# 15-MT7688AN_Ethernet-E.net
KiCad netlist of a schematic drawn in Altium Designer
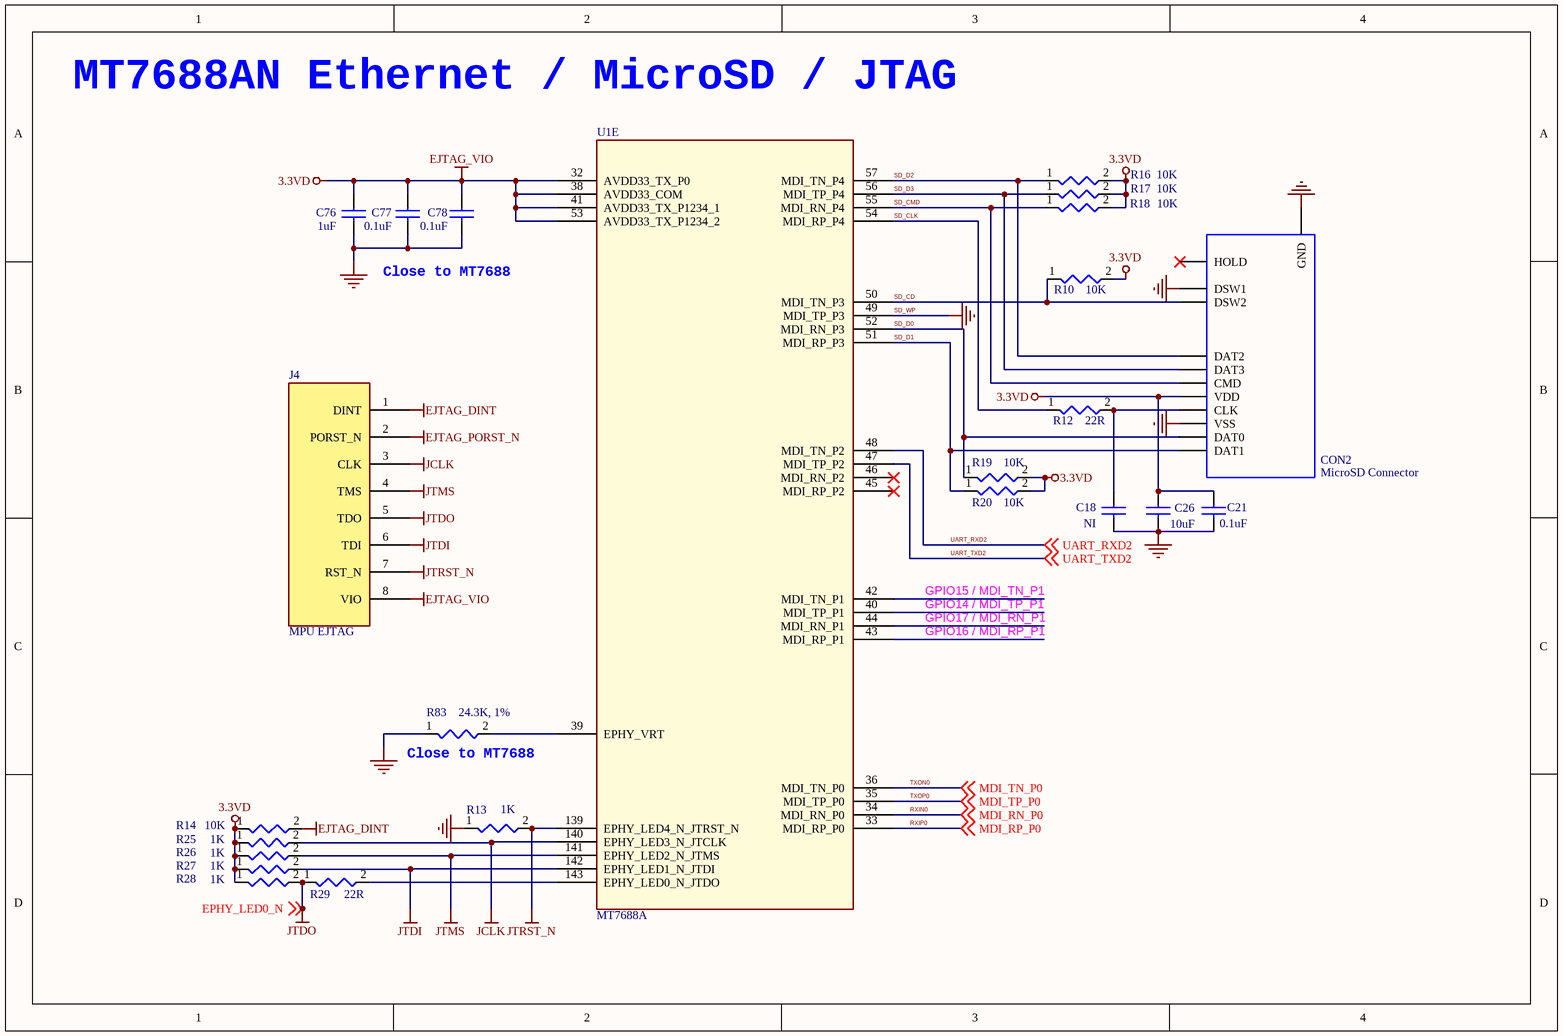
[diagram p0: 15-MT7688AN Ethernet-E.SchDoc]

(export (version "E")
  (design (tool "Eeschema 10.0.6"))
  (components
    (comp (ref "C18")
      (value "NI")
      (footprint "RLC 0201 M35")
      (libsource (lib "LinkIt Air+ (EK-7688AM+)") (part "CAP NP"))
    )
    (comp (ref "C21")
      (value "0.1uF")
      (footprint "RLC 0201 M35")
      (libsource (lib "LinkIt Air+ (EK-7688AM+)") (part "CAP NP"))
    )
    (comp (ref "C26")
      (value "10uF")
      (footprint "RLC 0402 M35")
      (libsource (lib "LinkIt Air+ (EK-7688AM+)") (part "CAP NP"))
    )
    (comp (ref "C76")
      (value "1uF")
      (footprint "RLC 0201 M35")
      (libsource (lib "LinkIt Air+ (EK-7688AM+)") (part "CAP NP"))
    )
    (comp (ref "C77")
      (value "0.1uF")
      (footprint "RLC 0201 M35")
      (libsource (lib "LinkIt Air+ (EK-7688AM+)") (part "CAP NP"))
    )
    (comp (ref "C78")
      (value "0.1uF")
      (footprint "RLC 0201 M35")
      (libsource (lib "LinkIt Air+ (EK-7688AM+)") (part "CAP NP"))
    )
    (comp (ref "CON2")
      (value "MicroSD Connector")
      (footprint "MICROSD-ST11S008V4H")
      (description "Micro SD Card H=1.25 (ST11S008V4H)")
      (libsource (lib "LinkIt Air+ (EK-7688AM+)") (part "MicroSD-ST11S008V4H"))
    )
    (comp (ref "J4")
      (value "MPU EJTAG")
      (footprint "MPU EJTAG")
      (libsource (lib "LinkIt Air+ (EK-7688AM+)") (part "MPU EJTAG"))
    )
    (comp (ref "R10")
      (value "10K")
      (footprint "RLC 0201 M35")
      (libsource (lib "LinkIt Air+ (EK-7688AM+)") (part "RES/0402_3"))
    )
    (comp (ref "R12")
      (value "22R")
      (footprint "RLC 0201 M35")
      (libsource (lib "LinkIt Air+ (EK-7688AM+)") (part "RES/0402_3"))
    )
    (comp (ref "R13")
      (value "1K")
      (footprint "RLC 0201 M35")
      (libsource (lib "LinkIt Air+ (EK-7688AM+)") (part "RES/0402_3"))
    )
    (comp (ref "R14")
      (value "10K")
      (footprint "RLC 0201 M35")
      (libsource (lib "LinkIt Air+ (EK-7688AM+)") (part "RES/0402_3"))
    )
    (comp (ref "R16")
      (value "10K")
      (footprint "RLC 0201 M35")
      (libsource (lib "LinkIt Air+ (EK-7688AM+)") (part "RES/0402_3"))
    )
    (comp (ref "R17")
      (value "10K")
      (footprint "RLC 0201 M35")
      (libsource (lib "LinkIt Air+ (EK-7688AM+)") (part "RES/0402_3"))
    )
    (comp (ref "R18")
      (value "10K")
      (footprint "RLC 0201 M35")
      (libsource (lib "LinkIt Air+ (EK-7688AM+)") (part "RES/0402_3"))
    )
    (comp (ref "R19")
      (value "10K")
      (footprint "RLC 0201 M35")
      (libsource (lib "LinkIt Air+ (EK-7688AM+)") (part "RES/0402_3"))
    )
    (comp (ref "R20")
      (value "10K")
      (footprint "RLC 0201 M35")
      (libsource (lib "LinkIt Air+ (EK-7688AM+)") (part "RES/0402_3"))
    )
    (comp (ref "R25")
      (value "1K")
      (footprint "RLC 0201 M35")
      (libsource (lib "LinkIt Air+ (EK-7688AM+)") (part "RES/0402_3"))
    )
    (comp (ref "R26")
      (value "1K")
      (footprint "RLC 0201 M35")
      (libsource (lib "LinkIt Air+ (EK-7688AM+)") (part "RES/0402_3"))
    )
    (comp (ref "R27")
      (value "1K")
      (footprint "RLC 0201 M35")
      (libsource (lib "LinkIt Air+ (EK-7688AM+)") (part "RES/0402_3"))
    )
    (comp (ref "R28")
      (value "1K")
      (footprint "RLC 0201 M35")
      (libsource (lib "LinkIt Air+ (EK-7688AM+)") (part "RES/0402_3"))
    )
    (comp (ref "R29")
      (value "22R")
      (footprint "RLC 0201 M35")
      (libsource (lib "LinkIt Air+ (EK-7688AM+)") (part "RES/0402_3"))
    )
    (comp (ref "R83")
      (value "24.3K, 1%")
      (footprint "RLC 0201 M35")
      (libsource (lib "LinkIt Air+ (EK-7688AM+)") (part "RES/0402_3"))
    )
    (comp (ref "U1")
      (value "MT7688A")
      (footprint "MT7628AN$2F$DRQFN156$2F$SMD$2F$P0.5$2F$12X12")
      (libsource (lib "LinkIt Air+ (EK-7688AM+)") (part "MT7620N-n_26"))
    )
  )
  (nets
    (net (code "1") (name "/GPIO14 {slash} MDI_TP_P1") (class "Default")
      (node (ref "U1") (pin "40") (pinfunction "MDI_TP_P1_40") (pintype "passive"))
    )
    (net (code "2") (name "/GPIO15 {slash} MDI_TN_P1") (class "Default")
      (node (ref "U1") (pin "42") (pinfunction "MDI_TN_P1_42") (pintype "passive"))
    )
    (net (code "3") (name "/GPIO16 {slash} MDI_RP_P1") (class "Default")
      (node (ref "U1") (pin "43") (pinfunction "MDI_RP_P1_43") (pintype "passive"))
    )
    (net (code "4") (name "/GPIO17 {slash} MDI_RN_P1") (class "Default")
      (node (ref "U1") (pin "44") (pinfunction "MDI_RN_P1_44") (pintype "passive"))
    )
    (net (code "5") (name "/SD_CD") (class "Default")
      (node (ref "CON2") (pin "10") (pinfunction "DSW2_10") (pintype "passive"))
      (node (ref "R10") (pin "1") (pinfunction "1_1") (pintype "passive"))
      (node (ref "U1") (pin "50") (pinfunction "MDI_TN_P3_50") (pintype "passive"))
    )
    (net (code "6") (name "/SD_CLK") (class "Default")
      (node (ref "R12") (pin "1") (pinfunction "1_1") (pintype "passive"))
      (node (ref "U1") (pin "54") (pinfunction "MDI_RP_P4_54") (pintype "passive"))
    )
    (net (code "7") (name "/SD_CMD") (class "Default")
      (node (ref "CON2") (pin "3") (pinfunction "CMD_3") (pintype "passive"))
      (node (ref "R18") (pin "1") (pinfunction "1_1") (pintype "passive"))
      (node (ref "U1") (pin "55") (pinfunction "MDI_RN_P4_55") (pintype "passive"))
    )
    (net (code "8") (name "/SD_D0") (class "Default")
      (node (ref "CON2") (pin "7") (pinfunction "DAT0_7") (pintype "passive"))
      (node (ref "R19") (pin "1") (pinfunction "1_1") (pintype "passive"))
      (node (ref "U1") (pin "52") (pinfunction "MDI_RN_P3_52") (pintype "passive"))
    )
    (net (code "9") (name "/SD_D1") (class "Default")
      (node (ref "CON2") (pin "8") (pinfunction "DAT1_8") (pintype "passive"))
      (node (ref "R20") (pin "1") (pinfunction "1_1") (pintype "passive"))
      (node (ref "U1") (pin "51") (pinfunction "MDI_RP_P3_51") (pintype "passive"))
    )
    (net (code "10") (name "/SD_D2") (class "Default")
      (node (ref "CON2") (pin "1") (pinfunction "DAT2_1") (pintype "passive"))
      (node (ref "R16") (pin "1") (pinfunction "1_1") (pintype "passive"))
      (node (ref "U1") (pin "57") (pinfunction "MDI_TN_P4_57") (pintype "passive"))
    )
    (net (code "11") (name "/SD_D3") (class "Default")
      (node (ref "CON2") (pin "2") (pinfunction "DAT3_2") (pintype "passive"))
      (node (ref "R17") (pin "1") (pinfunction "1_1") (pintype "passive"))
      (node (ref "U1") (pin "56") (pinfunction "MDI_TP_P4_56") (pintype "passive"))
    )
    (net (code "12") (name "3.3VD") (class "Default")
      (node (ref "C21") (pin "1") (pinfunction "1_1") (pintype "passive"))
      (node (ref "C26") (pin "1") (pinfunction "1_1") (pintype "passive"))
      (node (ref "C76") (pin "1") (pinfunction "1_1") (pintype "passive"))
      (node (ref "C77") (pin "1") (pinfunction "1_1") (pintype "passive"))
      (node (ref "C78") (pin "1") (pinfunction "1_1") (pintype "passive"))
      (node (ref "CON2") (pin "4") (pinfunction "VDD_4") (pintype "passive"))
      (node (ref "J4") (pin "8") (pinfunction "VIO_8") (pintype "passive"))
      (node (ref "R10") (pin "2") (pinfunction "2_2") (pintype "passive"))
      (node (ref "R14") (pin "1") (pinfunction "1_1") (pintype "passive"))
      (node (ref "R16") (pin "2") (pinfunction "2_2") (pintype "passive"))
      (node (ref "R17") (pin "2") (pinfunction "2_2") (pintype "passive"))
      (node (ref "R18") (pin "2") (pinfunction "2_2") (pintype "passive"))
      (node (ref "R19") (pin "2") (pinfunction "2_2") (pintype "passive"))
      (node (ref "R20") (pin "2") (pinfunction "2_2") (pintype "passive"))
      (node (ref "R25") (pin "1") (pinfunction "1_1") (pintype "passive"))
      (node (ref "R26") (pin "1") (pinfunction "1_1") (pintype "passive"))
      (node (ref "R27") (pin "1") (pinfunction "1_1") (pintype "passive"))
      (node (ref "R28") (pin "1") (pinfunction "1_1") (pintype "passive"))
      (node (ref "U1") (pin "32") (pinfunction "AVDD33_TX_P0_32") (pintype "power_in"))
      (node (ref "U1") (pin "38") (pinfunction "AVDD33_COM_38") (pintype "power_in"))
      (node (ref "U1") (pin "41") (pinfunction "AVDD33_TX_P1234_1_41") (pintype "power_in"))
      (node (ref "U1") (pin "53") (pinfunction "AVDD33_TX_P1234_2_53") (pintype "power_in"))
    )
    (net (code "13") (name "EJTAG_DINT") (class "Default")
      (node (ref "J4") (pin "1") (pinfunction "DINT_1") (pintype "passive"))
      (node (ref "R14") (pin "2") (pinfunction "2_2") (pintype "passive"))
    )
    (net (code "14") (name "EJTAG_PORST_N") (class "Default")
      (node (ref "J4") (pin "2") (pinfunction "PORST_N_2") (pintype "passive"))
    )
    (net (code "15") (name "EPHY_LED0_N") (class "Default")
      (node (ref "J4") (pin "5") (pinfunction "TDO_5") (pintype "passive"))
      (node (ref "R28") (pin "2") (pinfunction "2_2") (pintype "passive"))
      (node (ref "R29") (pin "1") (pinfunction "1_1") (pintype "passive"))
    )
    (net (code "16") (name "GND") (class "Default")
      (node (ref "C18") (pin "2") (pinfunction "2_2") (pintype "passive"))
      (node (ref "C21") (pin "2") (pinfunction "2_2") (pintype "passive"))
      (node (ref "C26") (pin "2") (pinfunction "2_2") (pintype "passive"))
      (node (ref "C76") (pin "2") (pinfunction "2_2") (pintype "passive"))
      (node (ref "C77") (pin "2") (pinfunction "2_2") (pintype "passive"))
      (node (ref "C78") (pin "2") (pinfunction "2_2") (pintype "passive"))
      (node (ref "CON2") (pin "11") (pinfunction "DSW1_11") (pintype "passive"))
      (node (ref "CON2") (pin "14") (pinfunction "GND_14") (pintype "passive"))
      (node (ref "CON2") (pin "6") (pinfunction "VSS_6") (pintype "passive"))
      (node (ref "R13") (pin "1") (pinfunction "1_1") (pintype "passive"))
      (node (ref "R83") (pin "1") (pinfunction "1_1") (pintype "passive"))
      (node (ref "U1") (pin "49") (pinfunction "MDI_TP_P3_49") (pintype "passive"))
    )
    (net (code "17") (name "JCLK") (class "Default")
      (node (ref "J4") (pin "3") (pinfunction "CLK_3") (pintype "passive"))
      (node (ref "R25") (pin "2") (pinfunction "2_2") (pintype "passive"))
      (node (ref "U1") (pin "140") (pinfunction "EPHY_LED3_N_JTCLK_140") (pintype "passive"))
    )
    (net (code "18") (name "JTDI") (class "Default")
      (node (ref "J4") (pin "6") (pinfunction "TDI_6") (pintype "passive"))
      (node (ref "R27") (pin "2") (pinfunction "2_2") (pintype "passive"))
      (node (ref "U1") (pin "142") (pinfunction "EPHY_LED1_N_JTDI_142") (pintype "passive"))
    )
    (net (code "19") (name "JTMS") (class "Default")
      (node (ref "J4") (pin "4") (pinfunction "TMS_4") (pintype "passive"))
      (node (ref "R26") (pin "2") (pinfunction "2_2") (pintype "passive"))
      (node (ref "U1") (pin "141") (pinfunction "EPHY_LED2_N_JTMS_141") (pintype "passive"))
    )
    (net (code "20") (name "JTRST_N") (class "Default")
      (node (ref "J4") (pin "7") (pinfunction "RST_N_7") (pintype "passive"))
      (node (ref "R13") (pin "2") (pinfunction "2_2") (pintype "passive"))
      (node (ref "U1") (pin "139") (pinfunction "EPHY_LED4_N_JTRST_N_139") (pintype "passive"))
    )
    (net (code "21") (name "MDI_RN_P0") (class "Default")
      (node (ref "U1") (pin "34") (pinfunction "MDI_RN_P0_34") (pintype "passive"))
    )
    (net (code "22") (name "MDI_RP_P0") (class "Default")
      (node (ref "U1") (pin "33") (pinfunction "MDI_RP_P0_33") (pintype "passive"))
    )
    (net (code "23") (name "MDI_TN_P0") (class "Default")
      (node (ref "U1") (pin "36") (pinfunction "MDI_TN_P0_36") (pintype "passive"))
    )
    (net (code "24") (name "MDI_TP_P0") (class "Default")
      (node (ref "U1") (pin "35") (pinfunction "MDI_TP_P0_35") (pintype "passive"))
    )
    (net (code "25") (name "Net-(CON2-CLK)") (class "Default")
      (node (ref "C18") (pin "1") (pinfunction "1_1") (pintype "passive"))
      (node (ref "CON2") (pin "5") (pinfunction "CLK_5") (pintype "passive"))
      (node (ref "R12") (pin "2") (pinfunction "2_2") (pintype "passive"))
    )
    (net (code "26") (name "Net-(U1E-EPHY_LED0_N_JTDO)") (class "Default")
      (node (ref "R29") (pin "2") (pinfunction "2_2") (pintype "passive"))
      (node (ref "U1") (pin "143") (pinfunction "EPHY_LED0_N_JTDO_143") (pintype "passive"))
    )
    (net (code "27") (name "Net-(U1E-EPHY_VRT)") (class "Default")
      (node (ref "R83") (pin "2") (pinfunction "2_2") (pintype "passive"))
      (node (ref "U1") (pin "39") (pinfunction "EPHY_VRT_39") (pintype "passive"))
    )
    (net (code "28") (name "UART_RXD2") (class "Default")
      (node (ref "U1") (pin "48") (pinfunction "MDI_TN_P2_48") (pintype "passive"))
    )
    (net (code "29") (name "UART_TXD2") (class "Default")
      (node (ref "U1") (pin "47") (pinfunction "MDI_TP_P2_47") (pintype "passive"))
    )
    (net (code "30") (name "unconnected-(CON2-HOLD-Pad12)") (class "Default")
      (node (ref "CON2") (pin "12") (pinfunction "HOLD_12") (pintype "passive+no_connect"))
    )
    (net (code "31") (name "unconnected-(U1E-MDI_RN_P2-Pad46)") (class "Default")
      (node (ref "U1") (pin "46") (pinfunction "MDI_RN_P2_46") (pintype "passive+no_connect"))
    )
    (net (code "32") (name "unconnected-(U1E-MDI_RP_P2-Pad45)") (class "Default")
      (node (ref "U1") (pin "45") (pinfunction "MDI_RP_P2_45") (pintype "passive+no_connect"))
    )
  )
)
